# ukmarsbot-line-sensor-half-size-V2.net
KiCad netlist of a schematic drawn in EAGLE
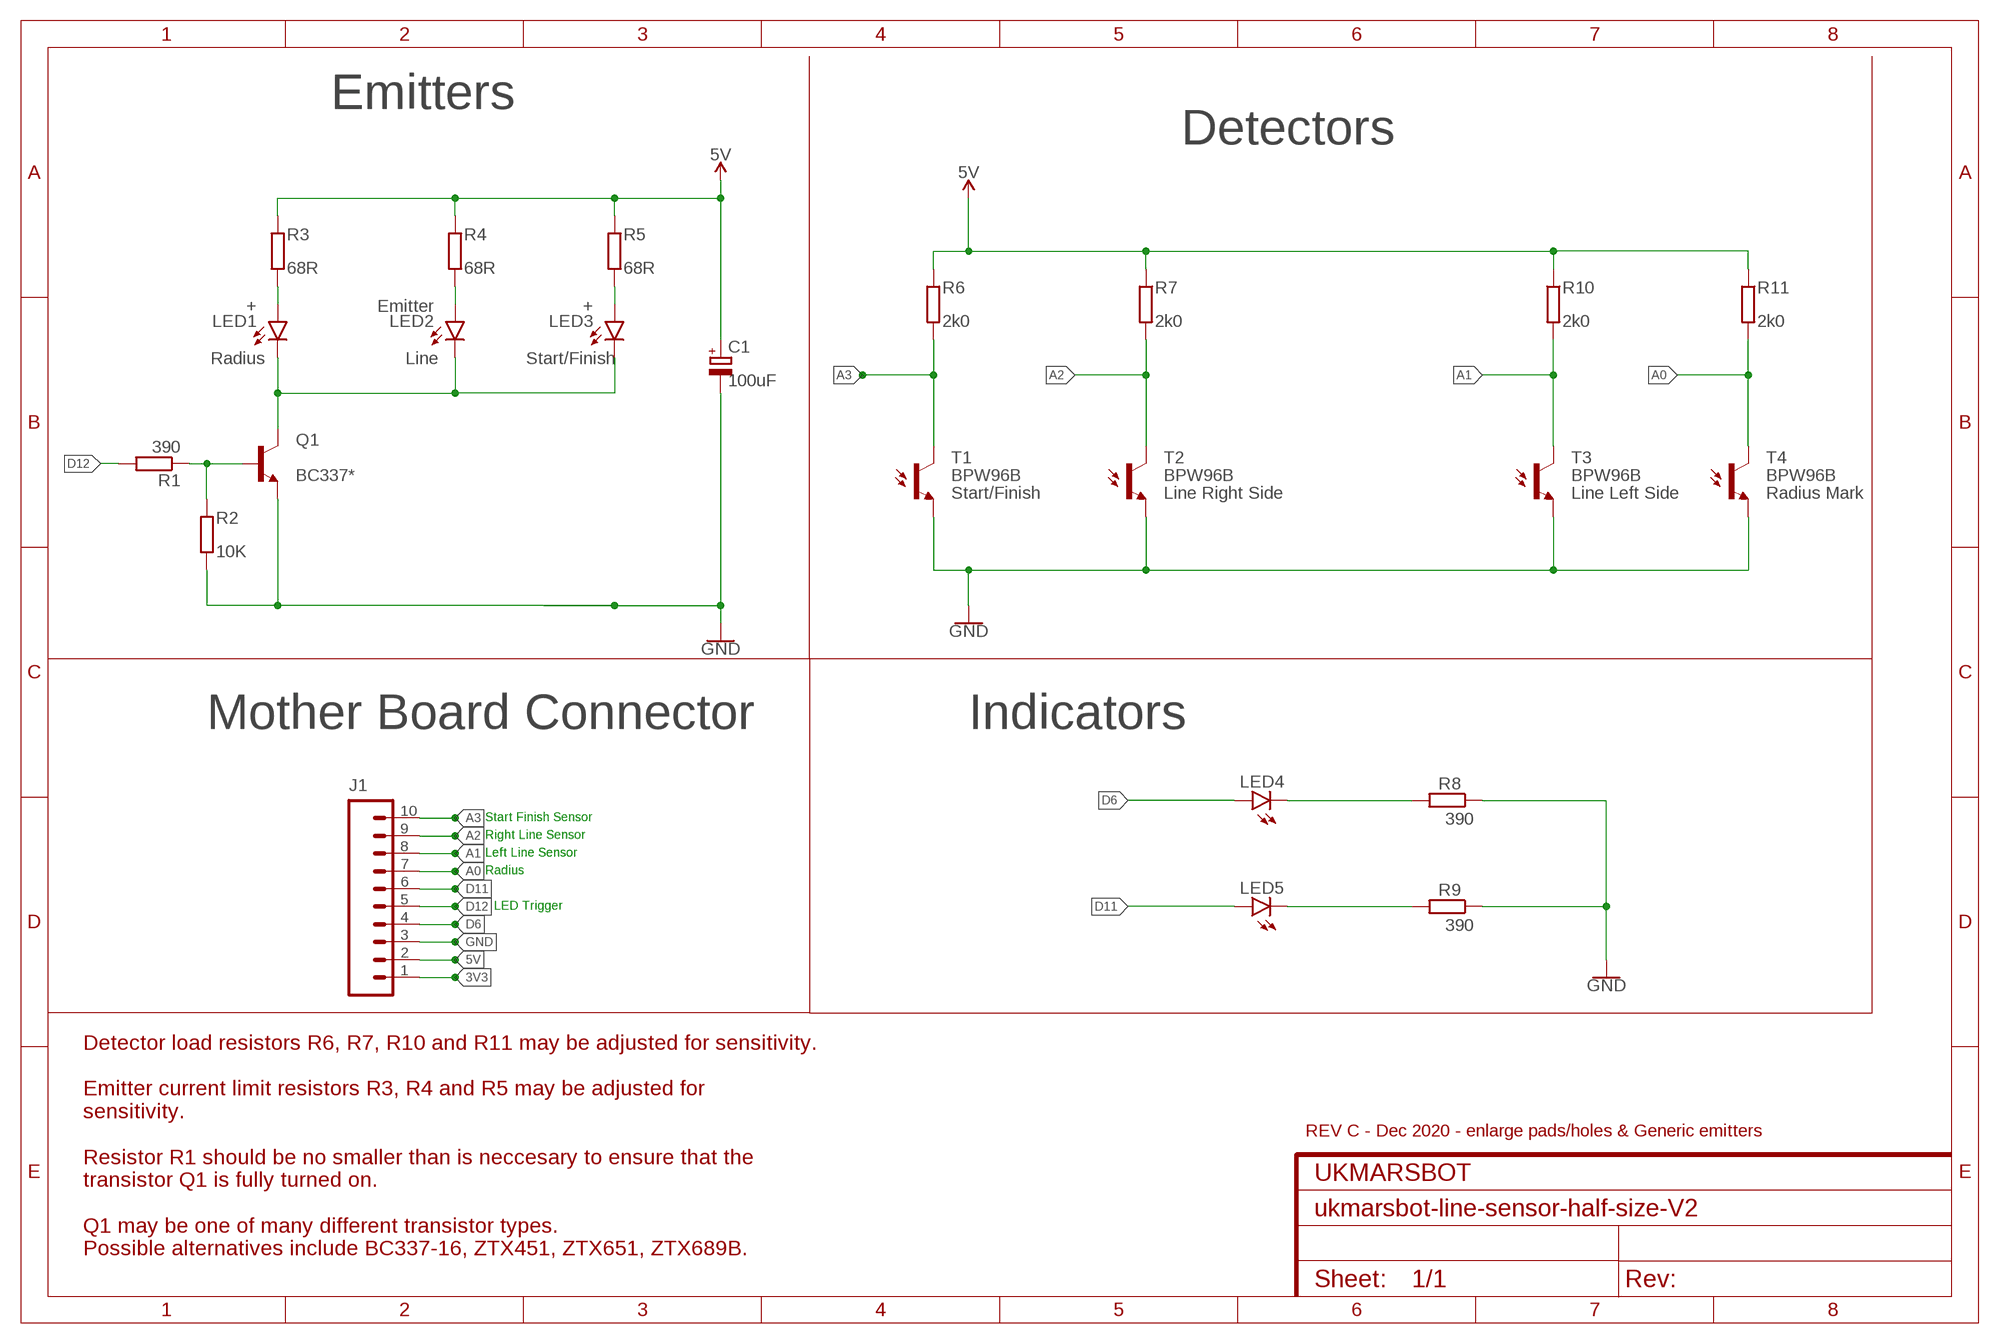
[diagram p0: schematic, sheet 1]

(export (version "E")
  (design (tool "Eeschema 10.0.6"))
  (components
    (comp (ref "C1")
      (value "100uF")
      (footprint "eagle-import:E2,5-7")
      (libsource (lib "eagle-import") (part "CPOL-EUE2.5-7"))
    )
    (comp (ref "J1")
      (value "CONN_10\"")
      (footprint "eagle-import:1X10")
      (libsource (lib "eagle-import") (part "CONN_10{dblquote}"))
    )
    (comp (ref "LED1")
      (value "+")
      (footprint "eagle-import:LED_5MM")
      (libsource (lib "eagle-import") (part "LED5MM"))
    )
    (comp (ref "LED2")
      (value "Emitter")
      (footprint "eagle-import:LED_5MM")
      (libsource (lib "eagle-import") (part "LED5MM"))
    )
    (comp (ref "LED3")
      (value "+")
      (footprint "eagle-import:LED_5MM")
      (libsource (lib "eagle-import") (part "LED5MM"))
    )
    (comp (ref "LED4")
      (value "LED3MM")
      (footprint "eagle-import:LED_3MM")
      (libsource (lib "eagle-import") (part "LED3MM"))
    )
    (comp (ref "LED5")
      (value "LED3MM")
      (footprint "eagle-import:LED_3MM")
      (libsource (lib "eagle-import") (part "LED3MM"))
    )
    (comp (ref "Q1")
      (value "BC337*")
      (footprint "eagle-import:TO92-EBC")
      (libsource (lib "eagle-import") (part "TRANS_NPN"))
    )
    (comp (ref "R1")
      (value "390")
      (footprint "eagle-import:0207_7")
      (libsource (lib "eagle-import") (part "R-EU_0207/7"))
    )
    (comp (ref "R2")
      (value "10K")
      (footprint "eagle-import:0207_7")
      (libsource (lib "eagle-import") (part "R-EU_0207/7"))
    )
    (comp (ref "R3")
      (value "68R")
      (footprint "eagle-import:0207_7")
      (libsource (lib "eagle-import") (part "R-EU_0207/7"))
    )
    (comp (ref "R4")
      (value "68R")
      (footprint "eagle-import:0207_7")
      (libsource (lib "eagle-import") (part "R-EU_0207/7"))
    )
    (comp (ref "R5")
      (value "68R")
      (footprint "eagle-import:0207_7")
      (libsource (lib "eagle-import") (part "R-EU_0207/7"))
    )
    (comp (ref "R6")
      (value "2k0")
      (footprint "eagle-import:0207_7")
      (libsource (lib "eagle-import") (part "R-EU_0207/7"))
    )
    (comp (ref "R7")
      (value "2k0")
      (footprint "eagle-import:0207_7")
      (libsource (lib "eagle-import") (part "R-EU_0207/7"))
    )
    (comp (ref "R8")
      (value "390")
      (footprint "eagle-import:0207_7")
      (libsource (lib "eagle-import") (part "R-EU_0207/7"))
    )
    (comp (ref "R9")
      (value "390")
      (footprint "eagle-import:0207_7")
      (libsource (lib "eagle-import") (part "R-EU_0207/7"))
    )
    (comp (ref "R10")
      (value "2k0")
      (footprint "eagle-import:0207_7")
      (libsource (lib "eagle-import") (part "R-EU_0207/7"))
    )
    (comp (ref "R11")
      (value "2k0")
      (footprint "eagle-import:0207_7")
      (libsource (lib "eagle-import") (part "R-EU_0207/7"))
    )
    (comp (ref "T1")
      (value "BPW96B")
      (footprint "eagle-import:PHOTOTRANSISTOR_5MM")
      (libsource (lib "eagle-import") (part "PHOTOTRANSISTOR5MM"))
    )
    (comp (ref "T2")
      (value "BPW96B")
      (footprint "eagle-import:PHOTOTRANSISTOR_5MM")
      (libsource (lib "eagle-import") (part "PHOTOTRANSISTOR5MM"))
    )
    (comp (ref "T3")
      (value "BPW96B")
      (footprint "eagle-import:PHOTOTRANSISTOR_5MM")
      (libsource (lib "eagle-import") (part "PHOTOTRANSISTOR5MM"))
    )
    (comp (ref "T4")
      (value "BPW96B")
      (footprint "eagle-import:PHOTOTRANSISTOR_5MM")
      (libsource (lib "eagle-import") (part "PHOTOTRANSISTOR5MM"))
    )
  )
  (nets
    (net (code "1") (name "3V3") (class "Default")
      (node (ref "J1") (pin "1") (pinfunction "1_1") (pintype "passive"))
    )
    (net (code "2") (name "5V") (class "Default")
      (node (ref "C1") (pin "+") (pinfunction "+_+") (pintype "passive"))
      (node (ref "J1") (pin "2") (pinfunction "2_2") (pintype "passive"))
      (node (ref "R10") (pin "1") (pinfunction "1_1") (pintype "passive"))
      (node (ref "R11") (pin "1") (pinfunction "1_1") (pintype "passive"))
      (node (ref "R3") (pin "2") (pinfunction "2_2") (pintype "passive"))
      (node (ref "R4") (pin "2") (pinfunction "2_2") (pintype "passive"))
      (node (ref "R5") (pin "2") (pinfunction "2_2") (pintype "passive"))
      (node (ref "R6") (pin "1") (pinfunction "1_1") (pintype "passive"))
      (node (ref "R7") (pin "1") (pinfunction "1_1") (pintype "passive"))
    )
    (net (code "3") (name "A0") (class "Default")
      (node (ref "J1") (pin "7") (pinfunction "7_7") (pintype "passive"))
      (node (ref "R11") (pin "2") (pinfunction "2_2") (pintype "passive"))
      (node (ref "T4") (pin "C") (pinfunction "C_C") (pintype "passive"))
    )
    (net (code "4") (name "A1") (class "Default")
      (node (ref "J1") (pin "8") (pinfunction "8_8") (pintype "passive"))
      (node (ref "R10") (pin "2") (pinfunction "2_2") (pintype "passive"))
      (node (ref "T3") (pin "C") (pinfunction "C_C") (pintype "passive"))
    )
    (net (code "5") (name "A2") (class "Default")
      (node (ref "J1") (pin "9") (pinfunction "9_9") (pintype "passive"))
      (node (ref "R7") (pin "2") (pinfunction "2_2") (pintype "passive"))
      (node (ref "T2") (pin "C") (pinfunction "C_C") (pintype "passive"))
    )
    (net (code "6") (name "A3") (class "Default")
      (node (ref "J1") (pin "10") (pinfunction "10_10") (pintype "passive"))
      (node (ref "R6") (pin "2") (pinfunction "2_2") (pintype "passive"))
      (node (ref "T1") (pin "C") (pinfunction "C_C") (pintype "passive"))
    )
    (net (code "7") (name "D6") (class "Default")
      (node (ref "J1") (pin "4") (pinfunction "4_4") (pintype "passive"))
      (node (ref "LED4") (pin "A") (pinfunction "A_A") (pintype "passive"))
    )
    (net (code "8") (name "D11") (class "Default")
      (node (ref "J1") (pin "6") (pinfunction "6_6") (pintype "passive"))
      (node (ref "LED5") (pin "A") (pinfunction "A_A") (pintype "passive"))
    )
    (net (code "9") (name "D12") (class "Default")
      (node (ref "J1") (pin "5") (pinfunction "5_5") (pintype "passive"))
      (node (ref "R1") (pin "2") (pinfunction "2_2") (pintype "passive"))
    )
    (net (code "10") (name "GND") (class "Default")
      (node (ref "C1") (pin "-") (pinfunction "-_-") (pintype "passive"))
      (node (ref "J1") (pin "3") (pinfunction "3_3") (pintype "passive"))
      (node (ref "Q1") (pin "E") (pinfunction "E_E") (pintype "passive"))
      (node (ref "R2") (pin "1") (pinfunction "1_1") (pintype "passive"))
      (node (ref "R8") (pin "1") (pinfunction "1_1") (pintype "passive"))
      (node (ref "R9") (pin "1") (pinfunction "1_1") (pintype "passive"))
      (node (ref "T1") (pin "E") (pinfunction "E_E") (pintype "passive"))
      (node (ref "T2") (pin "E") (pinfunction "E_E") (pintype "passive"))
      (node (ref "T3") (pin "E") (pinfunction "E_E") (pintype "passive"))
      (node (ref "T4") (pin "E") (pinfunction "E_E") (pintype "passive"))
    )
    (net (code "11") (name "Net-(LED1-C)") (class "Default")
      (node (ref "LED1") (pin "K") (pinfunction "C_K") (pintype "passive"))
      (node (ref "LED2") (pin "K") (pinfunction "C_K") (pintype "passive"))
      (node (ref "LED3") (pin "K") (pinfunction "C_K") (pintype "passive"))
      (node (ref "Q1") (pin "C") (pinfunction "C_C") (pintype "passive"))
    )
    (net (code "12") (name "Net-(LED1-PadA)") (class "Default")
      (node (ref "LED1") (pin "A") (pinfunction "A_A") (pintype "passive"))
      (node (ref "R3") (pin "1") (pinfunction "1_1") (pintype "passive"))
    )
    (net (code "13") (name "Net-(LED2-PadA)") (class "Default")
      (node (ref "LED2") (pin "A") (pinfunction "A_A") (pintype "passive"))
      (node (ref "R4") (pin "1") (pinfunction "1_1") (pintype "passive"))
    )
    (net (code "14") (name "Net-(LED3-PadA)") (class "Default")
      (node (ref "LED3") (pin "A") (pinfunction "A_A") (pintype "passive"))
      (node (ref "R5") (pin "1") (pinfunction "1_1") (pintype "passive"))
    )
    (net (code "15") (name "Net-(LED4-C)") (class "Default")
      (node (ref "LED4") (pin "K") (pinfunction "C_K") (pintype "passive"))
      (node (ref "R8") (pin "2") (pinfunction "2_2") (pintype "passive"))
    )
    (net (code "16") (name "Net-(LED5-C)") (class "Default")
      (node (ref "LED5") (pin "K") (pinfunction "C_K") (pintype "passive"))
      (node (ref "R9") (pin "2") (pinfunction "2_2") (pintype "passive"))
    )
    (net (code "17") (name "Net-(Q1-PadB)") (class "Default")
      (node (ref "Q1") (pin "B") (pinfunction "B_B") (pintype "passive"))
      (node (ref "R1") (pin "1") (pinfunction "1_1") (pintype "passive"))
      (node (ref "R2") (pin "2") (pinfunction "2_2") (pintype "passive"))
    )
  )
)
